# PCRemoteControl.net
KiCad netlist of a schematic drawn in EAGLE
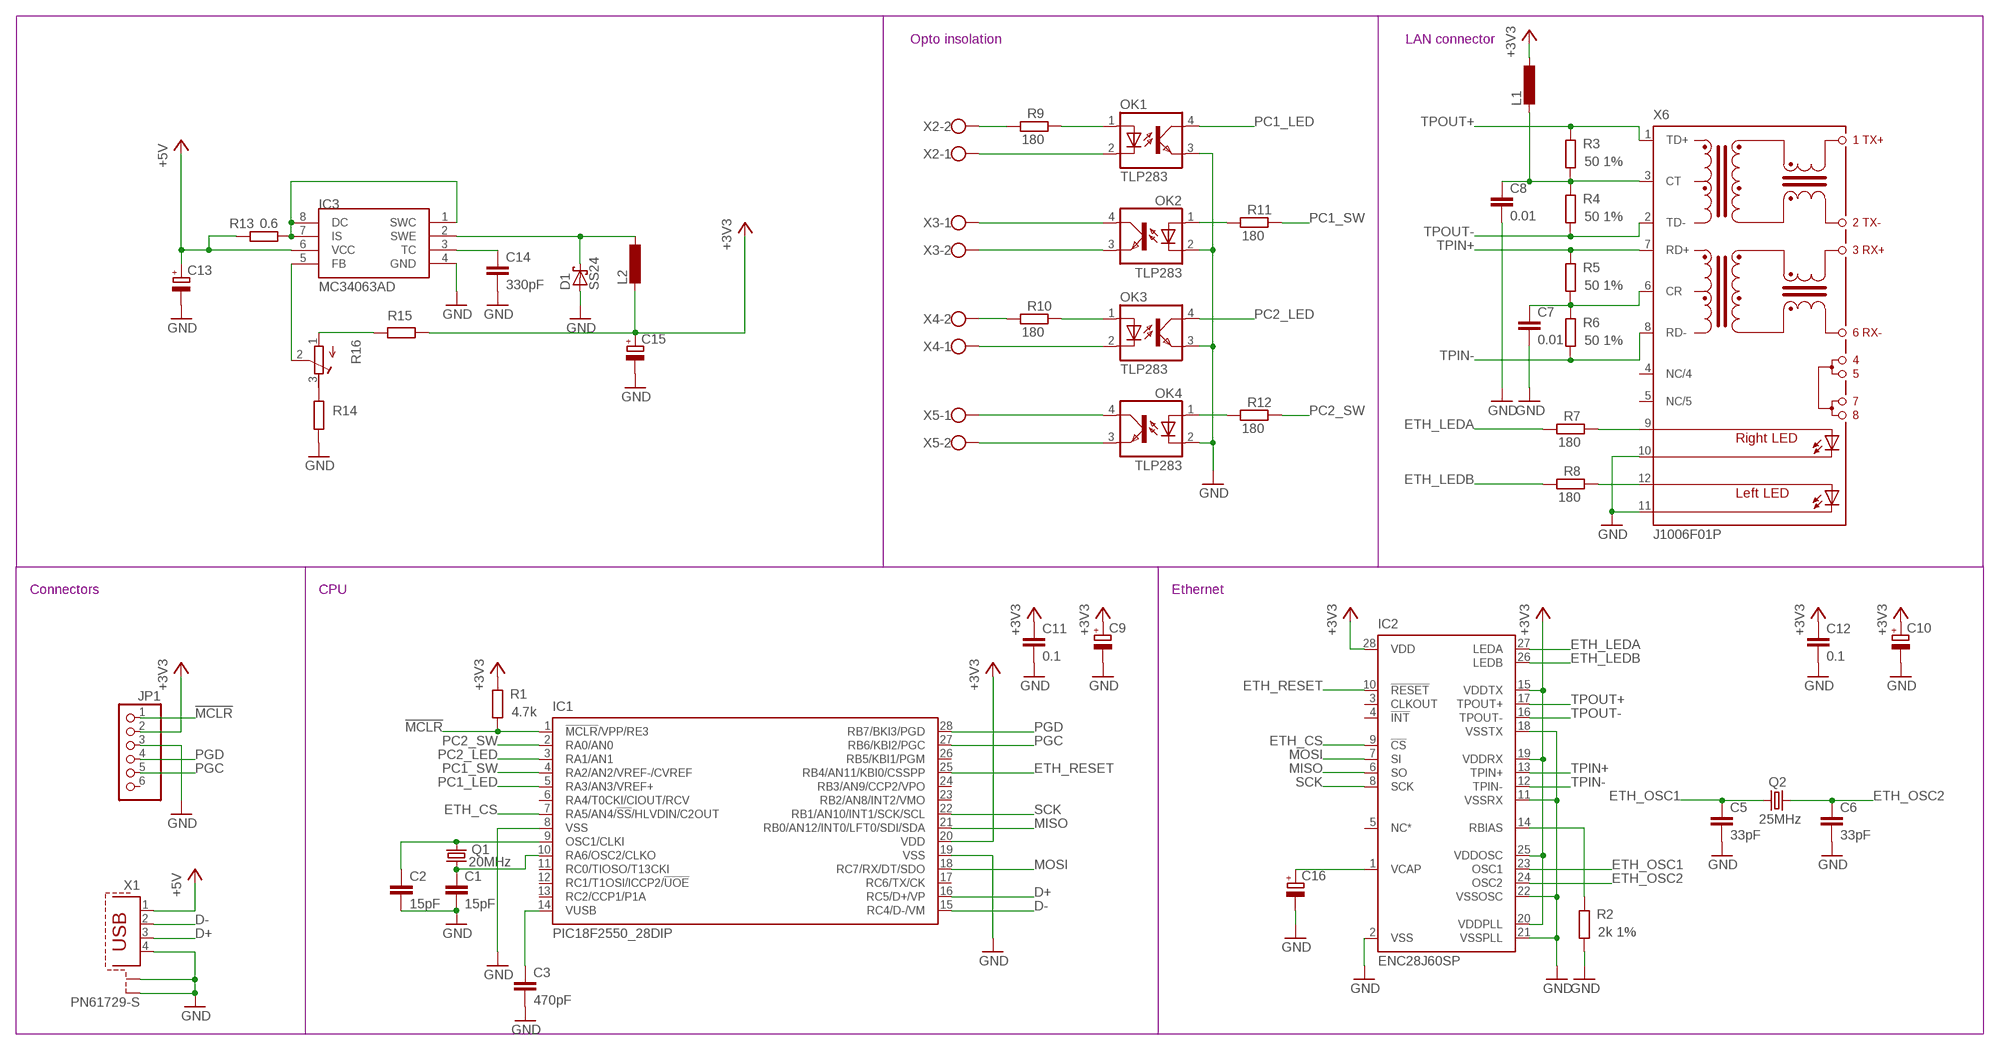
[diagram p0: schematic, sheet 1]

(export (version "E")
  (design (tool "Eeschema 10.0.6"))
  (components
    (comp (ref "C1")
      (value "15pF")
      (footprint "eagle-import:C1206")
      (libsource (lib "eagle-import") (part "C-EUC1206"))
    )
    (comp (ref "C2")
      (value "15pF")
      (footprint "eagle-import:C1206")
      (libsource (lib "eagle-import") (part "C-EUC1206"))
    )
    (comp (ref "C3")
      (value "470pF")
      (footprint "eagle-import:C1206")
      (libsource (lib "eagle-import") (part "C-EUC1206"))
    )
    (comp (ref "C5")
      (value "33pF")
      (footprint "eagle-import:C1206")
      (libsource (lib "eagle-import") (part "C-EUC1206"))
    )
    (comp (ref "C6")
      (value "33pF")
      (footprint "eagle-import:C1206")
      (libsource (lib "eagle-import") (part "C-EUC1206"))
    )
    (comp (ref "C7")
      (value "0.01")
      (footprint "eagle-import:C1206")
      (libsource (lib "eagle-import") (part "C-EUC1206"))
    )
    (comp (ref "C8")
      (value "0.01")
      (footprint "eagle-import:C1206")
      (libsource (lib "eagle-import") (part "C-EUC1206"))
    )
    (comp (ref "C9")
      (value "CPOL-EUSMCD")
      (footprint "eagle-import:SMC_D")
      (libsource (lib "eagle-import") (part "CPOL-EUSMCD"))
    )
    (comp (ref "C10")
      (value "CPOL-EUSMCD")
      (footprint "eagle-import:SMC_D")
      (libsource (lib "eagle-import") (part "CPOL-EUSMCD"))
    )
    (comp (ref "C11")
      (value "0.1")
      (footprint "eagle-import:C1206")
      (libsource (lib "eagle-import") (part "C-EUC1206"))
    )
    (comp (ref "C12")
      (value "0.1")
      (footprint "eagle-import:C1206")
      (libsource (lib "eagle-import") (part "C-EUC1206"))
    )
    (comp (ref "C13")
      (value "CPOL-EUSMCD")
      (footprint "eagle-import:SMC_D")
      (libsource (lib "eagle-import") (part "CPOL-EUSMCD"))
    )
    (comp (ref "C14")
      (value "330pF")
      (footprint "eagle-import:C1206")
      (libsource (lib "eagle-import") (part "C-EUC1206"))
    )
    (comp (ref "C15")
      (value "CPOL-EUSMCD")
      (footprint "eagle-import:SMC_D")
      (libsource (lib "eagle-import") (part "CPOL-EUSMCD"))
    )
    (comp (ref "C16")
      (value "CPOL-EUSMCA")
      (footprint "eagle-import:SMC_A")
      (libsource (lib "eagle-import") (part "CPOL-EUSMCA"))
    )
    (comp (ref "D1")
      (value "SS24")
      (footprint "eagle-import:SMB")
      (libsource (lib "eagle-import") (part "SCHOTTKY-DIODESMD"))
    )
    (comp (ref "IC1")
      (value "PIC18F2550_28DIP")
      (footprint "eagle-import:DIL28-3")
      (fields (field (name "MF") "MICROCHIP") (field (name "MPN") "PIC18F2550-I/SP"))
      (libsource (lib "eagle-import") (part "PIC18F2_28DIP550"))
    )
    (comp (ref "IC2")
      (value "ENC28J60SP")
      (footprint "eagle-import:DIL28-3")
      (fields (field (name "MF") "MICROCHIP") (field (name "MPN") "ENC28J60/SP"))
      (libsource (lib "eagle-import") (part "ENC28J60SP"))
    )
    (comp (ref "IC3")
      (value "MC34063AD")
      (footprint "eagle-import:SOIC8")
      (libsource (lib "eagle-import") (part "MC34063AD"))
    )
    (comp (ref "JP1")
      (value "PINHD-1X6")
      (footprint "eagle-import:1X06")
      (libsource (lib "eagle-import") (part "PINHD-1X6"))
    )
    (comp (ref "L1")
      (value "L-EUL3230M")
      (footprint "eagle-import:L3230M")
      (libsource (lib "eagle-import") (part "L-EUL3230M"))
    )
    (comp (ref "L2")
      (value "L-EUPIS2816")
      (footprint "eagle-import:PIS2816")
      (libsource (lib "eagle-import") (part "L-EUPIS2816"))
    )
    (comp (ref "OK1")
      (value "TLP283")
      (footprint "eagle-import:MINI-FLAT-4")
      (libsource (lib "eagle-import") (part "TLP283"))
    )
    (comp (ref "OK2")
      (value "TLP283")
      (footprint "eagle-import:MINI-FLAT-4")
      (libsource (lib "eagle-import") (part "TLP283"))
    )
    (comp (ref "OK3")
      (value "TLP283")
      (footprint "eagle-import:MINI-FLAT-4")
      (libsource (lib "eagle-import") (part "TLP283"))
    )
    (comp (ref "OK4")
      (value "TLP283")
      (footprint "eagle-import:MINI-FLAT-4")
      (libsource (lib "eagle-import") (part "TLP283"))
    )
    (comp (ref "Q1")
      (value "20MHz")
      (footprint "eagle-import:HC49_S")
      (libsource (lib "eagle-import") (part "CRYSTALHC49S"))
    )
    (comp (ref "Q2")
      (value "25MHz")
      (footprint "eagle-import:HC49_S")
      (libsource (lib "eagle-import") (part "CRYSTALHC49S"))
    )
    (comp (ref "R1")
      (value "4.7k")
      (footprint "eagle-import:R1206")
      (libsource (lib "eagle-import") (part "R-EU_R1206"))
    )
    (comp (ref "R2")
      (value "2k 1%")
      (footprint "eagle-import:R1206")
      (libsource (lib "eagle-import") (part "R-EU_R1206"))
    )
    (comp (ref "R3")
      (value "50 1%")
      (footprint "eagle-import:R1206")
      (libsource (lib "eagle-import") (part "R-EU_R1206"))
    )
    (comp (ref "R4")
      (value "50 1%")
      (footprint "eagle-import:R1206")
      (libsource (lib "eagle-import") (part "R-EU_R1206"))
    )
    (comp (ref "R5")
      (value "50 1%")
      (footprint "eagle-import:R1206")
      (libsource (lib "eagle-import") (part "R-EU_R1206"))
    )
    (comp (ref "R6")
      (value "50 1%")
      (footprint "eagle-import:R1206")
      (libsource (lib "eagle-import") (part "R-EU_R1206"))
    )
    (comp (ref "R7")
      (value "180")
      (footprint "eagle-import:R1206")
      (libsource (lib "eagle-import") (part "R-EU_R1206"))
    )
    (comp (ref "R8")
      (value "180")
      (footprint "eagle-import:R1206")
      (libsource (lib "eagle-import") (part "R-EU_R1206"))
    )
    (comp (ref "R9")
      (value "180")
      (footprint "eagle-import:R1206")
      (libsource (lib "eagle-import") (part "R-EU_R1206"))
    )
    (comp (ref "R10")
      (value "180")
      (footprint "eagle-import:R1206")
      (libsource (lib "eagle-import") (part "R-EU_R1206"))
    )
    (comp (ref "R11")
      (value "180")
      (footprint "eagle-import:R1206")
      (libsource (lib "eagle-import") (part "R-EU_R1206"))
    )
    (comp (ref "R12")
      (value "180")
      (footprint "eagle-import:R1206")
      (libsource (lib "eagle-import") (part "R-EU_R1206"))
    )
    (comp (ref "R13")
      (value "0.6")
      (footprint "eagle-import:R1206")
      (libsource (lib "eagle-import") (part "R-EU_R1206"))
    )
    (comp (ref "R14")
      (value "R-EU_R1206")
      (footprint "eagle-import:R1206")
      (libsource (lib "eagle-import") (part "R-EU_R1206"))
    )
    (comp (ref "R15")
      (value "R-EU_R1206")
      (footprint "eagle-import:R1206")
      (libsource (lib "eagle-import") (part "R-EU_R1206"))
    )
    (comp (ref "R16")
      (value "R-TRIMM4G/J")
      (footprint "eagle-import:RTRIM4G_J")
      (libsource (lib "eagle-import") (part "R-TRIMM4G/J"))
    )
    (comp (ref "X1")
      (value "PN61729-S")
      (footprint "eagle-import:PN61729-S")
      (libsource (lib "eagle-import") (part "PN61729-S"))
    )
    (comp (ref "X2")
      (value "W237-102")
      (footprint "eagle-import:W237-102")
      (fields (field (name "MPN") "237-102"))
      (libsource (lib "eagle-import") (part "W237-102"))
    )
    (comp (ref "X3")
      (value "W237-102")
      (footprint "eagle-import:W237-102")
      (fields (field (name "MPN") "237-102"))
      (libsource (lib "eagle-import") (part "W237-102"))
    )
    (comp (ref "X4")
      (value "W237-102")
      (footprint "eagle-import:W237-102")
      (fields (field (name "MPN") "237-102"))
      (libsource (lib "eagle-import") (part "W237-102"))
    )
    (comp (ref "X5")
      (value "W237-102")
      (footprint "eagle-import:W237-102")
      (fields (field (name "MPN") "237-102"))
      (libsource (lib "eagle-import") (part "W237-102"))
    )
    (comp (ref "X6")
      (value "J1006F01P")
      (footprint "eagle-import:J1")
      (libsource (lib "eagle-import") (part "J1006F01P"))
    )
  )
  (nets
    (net (code "1") (name "+3V3") (class "Default")
      (node (ref "C10") (pin "+") (pinfunction "+_+") (pintype "passive"))
      (node (ref "C11") (pin "1") (pinfunction "1_1") (pintype "passive"))
      (node (ref "C12") (pin "1") (pinfunction "1_1") (pintype "passive"))
      (node (ref "C15") (pin "+") (pinfunction "+_+") (pintype "passive"))
      (node (ref "C9") (pin "+") (pinfunction "+_+") (pintype "passive"))
      (node (ref "IC1") (pin "20") (pinfunction "VDD_20") (pintype "power_in"))
      (node (ref "IC2") (pin "15") (pinfunction "VDDTX_15") (pintype "input"))
      (node (ref "IC2") (pin "19") (pinfunction "VDDRX_19") (pintype "input"))
      (node (ref "IC2") (pin "20") (pinfunction "VDDPLL_20") (pintype "input"))
      (node (ref "IC2") (pin "25") (pinfunction "VDDOSC_25") (pintype "input"))
      (node (ref "IC2") (pin "28") (pinfunction "VDD_28") (pintype "input"))
      (node (ref "JP1") (pin "2") (pinfunction "2_2") (pintype "passive"))
      (node (ref "L1") (pin "1") (pinfunction "1_1") (pintype "passive"))
      (node (ref "L2") (pin "2") (pinfunction "2_2") (pintype "passive"))
      (node (ref "R1") (pin "2") (pinfunction "2_2") (pintype "passive"))
      (node (ref "R15") (pin "1") (pinfunction "1_1") (pintype "passive"))
    )
    (net (code "2") (name "+5V") (class "Default")
      (node (ref "C13") (pin "+") (pinfunction "+_+") (pintype "passive"))
      (node (ref "IC3") (pin "6") (pinfunction "VCC_6") (pintype "passive"))
      (node (ref "R13") (pin "2") (pinfunction "2_2") (pintype "passive"))
      (node (ref "X1") (pin "1") (pinfunction "1_1") (pintype "passive"))
    )
    (net (code "3") (name "/D+") (class "Default")
      (node (ref "IC1") (pin "16") (pinfunction "RC5/D+/VP_16") (pintype "bidirectional"))
      (node (ref "X1") (pin "3") (pinfunction "3_3") (pintype "passive"))
    )
    (net (code "4") (name "/D-") (class "Default")
      (node (ref "IC1") (pin "15") (pinfunction "RC4/D-/VM_15") (pintype "bidirectional"))
      (node (ref "X1") (pin "2") (pinfunction "2_2") (pintype "passive"))
    )
    (net (code "5") (name "/ETH_CS") (class "Default")
      (node (ref "IC1") (pin "7") (pinfunction "RA5/AN4/~{SS}/HLVDIN/C2OUT_7") (pintype "bidirectional"))
      (node (ref "IC2") (pin "9") (pinfunction "~{CS}_9") (pintype "input"))
    )
    (net (code "6") (name "/ETH_LEDA") (class "Default")
      (node (ref "IC2") (pin "27") (pinfunction "LEDA_27") (pintype "output"))
      (node (ref "R7") (pin "2") (pinfunction "2_2") (pintype "passive"))
    )
    (net (code "7") (name "/ETH_LEDB") (class "Default")
      (node (ref "IC2") (pin "26") (pinfunction "LEDB_26") (pintype "output"))
      (node (ref "R8") (pin "2") (pinfunction "2_2") (pintype "passive"))
    )
    (net (code "8") (name "/ETH_OSC1") (class "Default")
      (node (ref "C5") (pin "1") (pinfunction "1_1") (pintype "passive"))
      (node (ref "IC2") (pin "23") (pinfunction "OSC1_23") (pintype "input"))
      (node (ref "Q2") (pin "1") (pinfunction "1_1") (pintype "passive"))
    )
    (net (code "9") (name "/ETH_OSC2") (class "Default")
      (node (ref "C6") (pin "1") (pinfunction "1_1") (pintype "passive"))
      (node (ref "IC2") (pin "24") (pinfunction "OSC2_24") (pintype "output"))
      (node (ref "Q2") (pin "2") (pinfunction "2_2") (pintype "passive"))
    )
    (net (code "10") (name "/ETH_RESET") (class "Default")
      (node (ref "IC1") (pin "25") (pinfunction "RB4/AN11/KBI0/CSSPP_25") (pintype "bidirectional"))
      (node (ref "IC2") (pin "10") (pinfunction "~{RESET}_10") (pintype "input"))
    )
    (net (code "11") (name "/MISO") (class "Default")
      (node (ref "IC1") (pin "21") (pinfunction "RB0/AN12/INT0/LFT0/SDI/SDA_21") (pintype "bidirectional"))
      (node (ref "IC2") (pin "6") (pinfunction "SO_6") (pintype "output"))
    )
    (net (code "12") (name "/MOSI") (class "Default")
      (node (ref "IC1") (pin "18") (pinfunction "RC7/RX/DT/SDO_18") (pintype "bidirectional"))
      (node (ref "IC2") (pin "7") (pinfunction "SI_7") (pintype "input"))
    )
    (net (code "13") (name "/PC1_LED") (class "Default")
      (node (ref "IC1") (pin "5") (pinfunction "RA3/AN3/VREF+_5") (pintype "bidirectional"))
      (node (ref "OK1") (pin "4") (pinfunction "COL_4") (pintype "passive"))
    )
    (net (code "14") (name "/PC1_SW") (class "Default")
      (node (ref "IC1") (pin "4") (pinfunction "RA2/AN2/VREF-/CVREF_4") (pintype "bidirectional"))
      (node (ref "R11") (pin "1") (pinfunction "1_1") (pintype "passive"))
    )
    (net (code "15") (name "/PC2_LED") (class "Default")
      (node (ref "IC1") (pin "3") (pinfunction "RA1/AN1_3") (pintype "bidirectional"))
      (node (ref "OK3") (pin "4") (pinfunction "COL_4") (pintype "passive"))
    )
    (net (code "16") (name "/PC2_SW") (class "Default")
      (node (ref "IC1") (pin "2") (pinfunction "RA0/AN0_2") (pintype "bidirectional"))
      (node (ref "R12") (pin "1") (pinfunction "1_1") (pintype "passive"))
    )
    (net (code "17") (name "/PGC") (class "Default")
      (node (ref "IC1") (pin "27") (pinfunction "RB6/KBI2/PGC_27") (pintype "bidirectional"))
      (node (ref "JP1") (pin "5") (pinfunction "5_5") (pintype "passive"))
    )
    (net (code "18") (name "/PGD") (class "Default")
      (node (ref "IC1") (pin "28") (pinfunction "RB7/BKI3/PGD_28") (pintype "bidirectional"))
      (node (ref "JP1") (pin "4") (pinfunction "4_4") (pintype "passive"))
    )
    (net (code "19") (name "/SCK") (class "Default")
      (node (ref "IC1") (pin "22") (pinfunction "RB1/AN10/INT1/SCK/SCL_22") (pintype "bidirectional"))
      (node (ref "IC2") (pin "8") (pinfunction "SCK_8") (pintype "input"))
    )
    (net (code "20") (name "/TPIN+") (class "Default")
      (node (ref "IC2") (pin "13") (pinfunction "TPIN+_13") (pintype "input"))
      (node (ref "R5") (pin "2") (pinfunction "2_2") (pintype "passive"))
      (node (ref "X6") (pin "7") (pinfunction "RD+_7") (pintype "input"))
    )
    (net (code "21") (name "/TPIN-") (class "Default")
      (node (ref "IC2") (pin "12") (pinfunction "TPIN-_12") (pintype "input"))
      (node (ref "R6") (pin "1") (pinfunction "1_1") (pintype "passive"))
      (node (ref "X6") (pin "8") (pinfunction "RD-_8") (pintype "input"))
    )
    (net (code "22") (name "/TPOUT+") (class "Default")
      (node (ref "IC2") (pin "17") (pinfunction "TPOUT+_17") (pintype "output"))
      (node (ref "R3") (pin "2") (pinfunction "2_2") (pintype "passive"))
      (node (ref "X6") (pin "1") (pinfunction "TD+_1") (pintype "input"))
    )
    (net (code "23") (name "/TPOUT-") (class "Default")
      (node (ref "IC2") (pin "16") (pinfunction "TPOUT-_16") (pintype "output"))
      (node (ref "R4") (pin "1") (pinfunction "1_1") (pintype "passive"))
      (node (ref "X6") (pin "2") (pinfunction "TD-_2") (pintype "input"))
    )
    (net (code "24") (name "/~{MCLR}") (class "Default")
      (node (ref "IC1") (pin "1") (pinfunction "~{MCLR}/VPP/RE3_1") (pintype "input"))
      (node (ref "JP1") (pin "1") (pinfunction "1_1") (pintype "passive"))
      (node (ref "R1") (pin "1") (pinfunction "1_1") (pintype "passive"))
    )
    (net (code "25") (name "GND") (class "Default")
      (node (ref "C1") (pin "2") (pinfunction "2_2") (pintype "passive"))
      (node (ref "C10") (pin "-") (pinfunction "-_-") (pintype "passive"))
      (node (ref "C11") (pin "2") (pinfunction "2_2") (pintype "passive"))
      (node (ref "C12") (pin "2") (pinfunction "2_2") (pintype "passive"))
      (node (ref "C13") (pin "-") (pinfunction "-_-") (pintype "passive"))
      (node (ref "C14") (pin "2") (pinfunction "2_2") (pintype "passive"))
      (node (ref "C15") (pin "-") (pinfunction "-_-") (pintype "passive"))
      (node (ref "C16") (pin "-") (pinfunction "-_-") (pintype "passive"))
      (node (ref "C2") (pin "2") (pinfunction "2_2") (pintype "passive"))
      (node (ref "C3") (pin "2") (pinfunction "2_2") (pintype "passive"))
      (node (ref "C5") (pin "2") (pinfunction "2_2") (pintype "passive"))
      (node (ref "C6") (pin "2") (pinfunction "2_2") (pintype "passive"))
      (node (ref "C7") (pin "2") (pinfunction "2_2") (pintype "passive"))
      (node (ref "C8") (pin "2") (pinfunction "2_2") (pintype "passive"))
      (node (ref "C9") (pin "-") (pinfunction "-_-") (pintype "passive"))
      (node (ref "D1") (pin "A") (pinfunction "A_A") (pintype "passive"))
      (node (ref "IC1") (pin "19") (pinfunction "VSS_19") (pintype "power_in"))
      (node (ref "IC1") (pin "8") (pinfunction "VSS_8") (pintype "power_in"))
      (node (ref "IC2") (pin "11") (pinfunction "VSSRX_11") (pintype "input"))
      (node (ref "IC2") (pin "18") (pinfunction "VSSTX_18") (pintype "input"))
      (node (ref "IC2") (pin "2") (pinfunction "VSS_2") (pintype "input"))
      (node (ref "IC2") (pin "21") (pinfunction "VSSPLL_21") (pintype "input"))
      (node (ref "IC2") (pin "22") (pinfunction "VSSOSC_22") (pintype "input"))
      (node (ref "IC3") (pin "4") (pinfunction "GND_4") (pintype "passive"))
      (node (ref "JP1") (pin "3") (pinfunction "3_3") (pintype "passive"))
      (node (ref "OK1") (pin "3") (pinfunction "EMIT_3") (pintype "passive"))
      (node (ref "OK2") (pin "2") (pinfunction "C_2") (pintype "passive"))
      (node (ref "OK3") (pin "3") (pinfunction "EMIT_3") (pintype "passive"))
      (node (ref "OK4") (pin "2") (pinfunction "C_2") (pintype "passive"))
      (node (ref "R14") (pin "1") (pinfunction "1_1") (pintype "passive"))
      (node (ref "R2") (pin "1") (pinfunction "1_1") (pintype "passive"))
      (node (ref "X1") (pin "4") (pinfunction "4_4") (pintype "passive"))
      (node (ref "X1") (pin "S1") (pinfunction "S1_S1") (pintype "passive"))
      (node (ref "X1") (pin "S2") (pinfunction "S2_S2") (pintype "passive"))
      (node (ref "X6") (pin "10") (pinfunction "C-R_10") (pintype "passive"))
      (node (ref "X6") (pin "11") (pinfunction "C-L_11") (pintype "passive"))
    )
    (net (code "26") (name "Net-(IC1-OSC1{slash}CLKI)") (class "Default")
      (node (ref "C2") (pin "1") (pinfunction "1_1") (pintype "passive"))
      (node (ref "IC1") (pin "9") (pinfunction "OSC1/CLKI_9") (pintype "input"))
      (node (ref "Q1") (pin "1") (pinfunction "1_1") (pintype "passive"))
    )
    (net (code "27") (name "Net-(IC1-RA6{slash}OSC2{slash}CLKO)") (class "Default")
      (node (ref "C1") (pin "1") (pinfunction "1_1") (pintype "passive"))
      (node (ref "IC1") (pin "10") (pinfunction "RA6/OSC2/CLKO_10") (pintype "output"))
      (node (ref "Q1") (pin "2") (pinfunction "2_2") (pintype "passive"))
    )
    (net (code "28") (name "Net-(IC1-VUSB)") (class "Default")
      (node (ref "C3") (pin "1") (pinfunction "1_1") (pintype "passive"))
      (node (ref "IC1") (pin "14") (pinfunction "VUSB_14") (pintype "bidirectional"))
    )
    (net (code "29") (name "Net-(IC2-RBIAS)") (class "Default")
      (node (ref "IC2") (pin "14") (pinfunction "RBIAS_14") (pintype "input"))
      (node (ref "R2") (pin "2") (pinfunction "2_2") (pintype "passive"))
    )
    (net (code "30") (name "Net-(IC2-VCAP)") (class "Default")
      (node (ref "C16") (pin "+") (pinfunction "+_+") (pintype "passive"))
      (node (ref "IC2") (pin "1") (pinfunction "VCAP_1") (pintype "input"))
    )
    (net (code "31") (name "Net-(IC3-DC)") (class "Default")
      (node (ref "IC3") (pin "1") (pinfunction "SWC_1") (pintype "passive"))
      (node (ref "IC3") (pin "7") (pinfunction "IS_7") (pintype "passive"))
      (node (ref "IC3") (pin "8") (pinfunction "DC_8") (pintype "passive"))
      (node (ref "R13") (pin "1") (pinfunction "1_1") (pintype "passive"))
    )
    (net (code "32") (name "Net-(IC3-FB)") (class "Default")
      (node (ref "IC3") (pin "5") (pinfunction "FB_5") (pintype "passive"))
      (node (ref "R16") (pin "2") (pinfunction "S_2") (pintype "passive"))
    )
    (net (code "33") (name "Net-(IC3-SWE)") (class "Default")
      (node (ref "D1") (pin "C") (pinfunction "C_C") (pintype "passive"))
      (node (ref "IC3") (pin "2") (pinfunction "SWE_2") (pintype "passive"))
      (node (ref "L2") (pin "1") (pinfunction "1_1") (pintype "passive"))
    )
    (net (code "34") (name "Net-(IC3-TC)") (class "Default")
      (node (ref "C14") (pin "1") (pinfunction "1_1") (pintype "passive"))
      (node (ref "IC3") (pin "3") (pinfunction "TC_3") (pintype "passive"))
    )
    (net (code "35") (name "Net-(OK1-A)") (class "Default")
      (node (ref "OK1") (pin "1") (pinfunction "A_1") (pintype "passive"))
      (node (ref "R9") (pin "1") (pinfunction "1_1") (pintype "passive"))
    )
    (net (code "36") (name "Net-(OK1-C)") (class "Default")
      (node (ref "OK1") (pin "2") (pinfunction "C_2") (pintype "passive"))
      (node (ref "X2") (pin "1") (pinfunction "KL_1") (pintype "passive"))
    )
    (net (code "37") (name "Net-(OK2-A)") (class "Default")
      (node (ref "OK2") (pin "1") (pinfunction "A_1") (pintype "passive"))
      (node (ref "R11") (pin "2") (pinfunction "2_2") (pintype "passive"))
    )
    (net (code "38") (name "Net-(OK2-COL)") (class "Default")
      (node (ref "OK2") (pin "4") (pinfunction "COL_4") (pintype "passive"))
      (node (ref "X3") (pin "1") (pinfunction "KL_1") (pintype "passive"))
    )
    (net (code "39") (name "Net-(OK2-EMIT)") (class "Default")
      (node (ref "OK2") (pin "3") (pinfunction "EMIT_3") (pintype "passive"))
      (node (ref "X3") (pin "2") (pinfunction "KL_2") (pintype "passive"))
    )
    (net (code "40") (name "Net-(OK3-A)") (class "Default")
      (node (ref "OK3") (pin "1") (pinfunction "A_1") (pintype "passive"))
      (node (ref "R10") (pin "1") (pinfunction "1_1") (pintype "passive"))
    )
    (net (code "41") (name "Net-(OK3-C)") (class "Default")
      (node (ref "OK3") (pin "2") (pinfunction "C_2") (pintype "passive"))
      (node (ref "X4") (pin "1") (pinfunction "KL_1") (pintype "passive"))
    )
    (net (code "42") (name "Net-(OK4-A)") (class "Default")
      (node (ref "OK4") (pin "1") (pinfunction "A_1") (pintype "passive"))
      (node (ref "R12") (pin "2") (pinfunction "2_2") (pintype "passive"))
    )
    (net (code "43") (name "Net-(OK4-COL)") (class "Default")
      (node (ref "OK4") (pin "4") (pinfunction "COL_4") (pintype "passive"))
      (node (ref "X5") (pin "1") (pinfunction "KL_1") (pintype "passive"))
    )
    (net (code "44") (name "Net-(OK4-EMIT)") (class "Default")
      (node (ref "OK4") (pin "3") (pinfunction "EMIT_3") (pintype "passive"))
      (node (ref "X5") (pin "2") (pinfunction "KL_2") (pintype "passive"))
    )
    (net (code "45") (name "Net-(R16-A)") (class "Default")
      (node (ref "R15") (pin "2") (pinfunction "2_2") (pintype "passive"))
      (node (ref "R16") (pin "1") (pinfunction "A_1") (pintype "passive"))
    )
    (net (code "46") (name "Net-(R16-E)") (class "Default")
      (node (ref "R14") (pin "2") (pinfunction "2_2") (pintype "passive"))
      (node (ref "R16") (pin "3") (pinfunction "E_3") (pintype "passive"))
    )
    (net (code "47") (name "Net-(X2B-KL)") (class "Default")
      (node (ref "R9") (pin "2") (pinfunction "2_2") (pintype "passive"))
      (node (ref "X2") (pin "2") (pinfunction "KL_2") (pintype "passive"))
    )
    (net (code "48") (name "Net-(X4B-KL)") (class "Default")
      (node (ref "R10") (pin "2") (pinfunction "2_2") (pintype "passive"))
      (node (ref "X4") (pin "2") (pinfunction "KL_2") (pintype "passive"))
    )
    (net (code "49") (name "Net-(X6-A-L)") (class "Default")
      (node (ref "R8") (pin "1") (pinfunction "1_1") (pintype "passive"))
      (node (ref "X6") (pin "12") (pinfunction "A-L_12") (pintype "passive"))
    )
    (net (code "50") (name "Net-(X6-A-R)") (class "Default")
      (node (ref "R7") (pin "1") (pinfunction "1_1") (pintype "passive"))
      (node (ref "X6") (pin "9") (pinfunction "A-R_9") (pintype "passive"))
    )
    (net (code "51") (name "Net-(X6-CR)") (class "Default")
      (node (ref "C7") (pin "1") (pinfunction "1_1") (pintype "passive"))
      (node (ref "R5") (pin "1") (pinfunction "1_1") (pintype "passive"))
      (node (ref "R6") (pin "2") (pinfunction "2_2") (pintype "passive"))
      (node (ref "X6") (pin "6") (pinfunction "CR_6") (pintype "input"))
    )
    (net (code "52") (name "Net-(X6-CT)") (class "Default")
      (node (ref "C8") (pin "1") (pinfunction "1_1") (pintype "passive"))
      (node (ref "L1") (pin "2") (pinfunction "2_2") (pintype "passive"))
      (node (ref "R3") (pin "1") (pinfunction "1_1") (pintype "passive"))
      (node (ref "R4") (pin "2") (pinfunction "2_2") (pintype "passive"))
      (node (ref "X6") (pin "3") (pinfunction "CT_3") (pintype "input"))
    )
    (net (code "53") (name "unconnected-(IC1-RA4{slash}T0CKI{slash}CIOUT{slash}RCV-Pad6)") (class "Default")
      (node (ref "IC1") (pin "6") (pinfunction "RA4/T0CKI/CIOUT/RCV_6") (pintype "bidirectional"))
    )
    (net (code "54") (name "unconnected-(IC1-RB2{slash}AN8{slash}INT2{slash}VMO-Pad23)") (class "Default")
      (node (ref "IC1") (pin "23") (pinfunction "RB2/AN8/INT2/VMO_23") (pintype "bidirectional"))
    )
    (net (code "55") (name "unconnected-(IC1-RB3{slash}AN9{slash}CCP2{slash}VPO-Pad24)") (class "Default")
      (node (ref "IC1") (pin "24") (pinfunction "RB3/AN9/CCP2/VPO_24") (pintype "bidirectional"))
    )
    (net (code "56") (name "unconnected-(IC1-RB5{slash}KBI1{slash}PGM-Pad26)") (class "Default")
      (node (ref "IC1") (pin "26") (pinfunction "RB5/KBI1/PGM_26") (pintype "bidirectional"))
    )
    (net (code "57") (name "unconnected-(IC1-RC0{slash}TIOSO{slash}T13CKI-Pad11)") (class "Default")
      (node (ref "IC1") (pin "11") (pinfunction "RC0/TIOSO/T13CKI_11") (pintype "bidirectional"))
    )
    (net (code "58") (name "unconnected-(IC1-RC1{slash}T1OSI{slash}ICCP2{slash}~{UOE}-Pad12)") (class "Default")
      (node (ref "IC1") (pin "12") (pinfunction "RC1/T1OSI/ICCP2/~{UOE}_12") (pintype "bidirectional"))
    )
    (net (code "59") (name "unconnected-(IC1-RC2{slash}CCP1{slash}P1A-Pad13)") (class "Default")
      (node (ref "IC1") (pin "13") (pinfunction "RC2/CCP1/P1A_13") (pintype "bidirectional"))
    )
    (net (code "60") (name "unconnected-(IC1-RC6{slash}TX{slash}CK-Pad17)") (class "Default")
      (node (ref "IC1") (pin "17") (pinfunction "RC6/TX/CK_17") (pintype "bidirectional"))
    )
    (net (code "61") (name "unconnected-(IC2-CLKOUT-Pad3)") (class "Default")
      (node (ref "IC2") (pin "3") (pinfunction "CLKOUT_3") (pintype "output"))
    )
    (net (code "62") (name "unconnected-(IC2-NC*-Pad5)") (class "Default")
      (node (ref "IC2") (pin "5") (pinfunction "NC*_5") (pintype "output"))
    )
    (net (code "63") (name "unconnected-(IC2-~{INT}-Pad4)") (class "Default")
      (node (ref "IC2") (pin "4") (pinfunction "~{INT}_4") (pintype "output"))
    )
    (net (code "64") (name "unconnected-(JP1-Pad6)") (class "Default")
      (node (ref "JP1") (pin "6") (pinfunction "6_6") (pintype "passive"))
    )
    (net (code "65") (name "unconnected-(X6-NC{slash}4-Pad4)") (class "Default")
      (node (ref "X6") (pin "4") (pinfunction "NC/4_4") (pintype "input"))
    )
    (net (code "66") (name "unconnected-(X6-NC{slash}5-Pad5)") (class "Default")
      (node (ref "X6") (pin "5") (pinfunction "NC/5_5") (pintype "input"))
    )
  )
)
